# main.net
KiCad netlist of a schematic drawn in Altium Designer
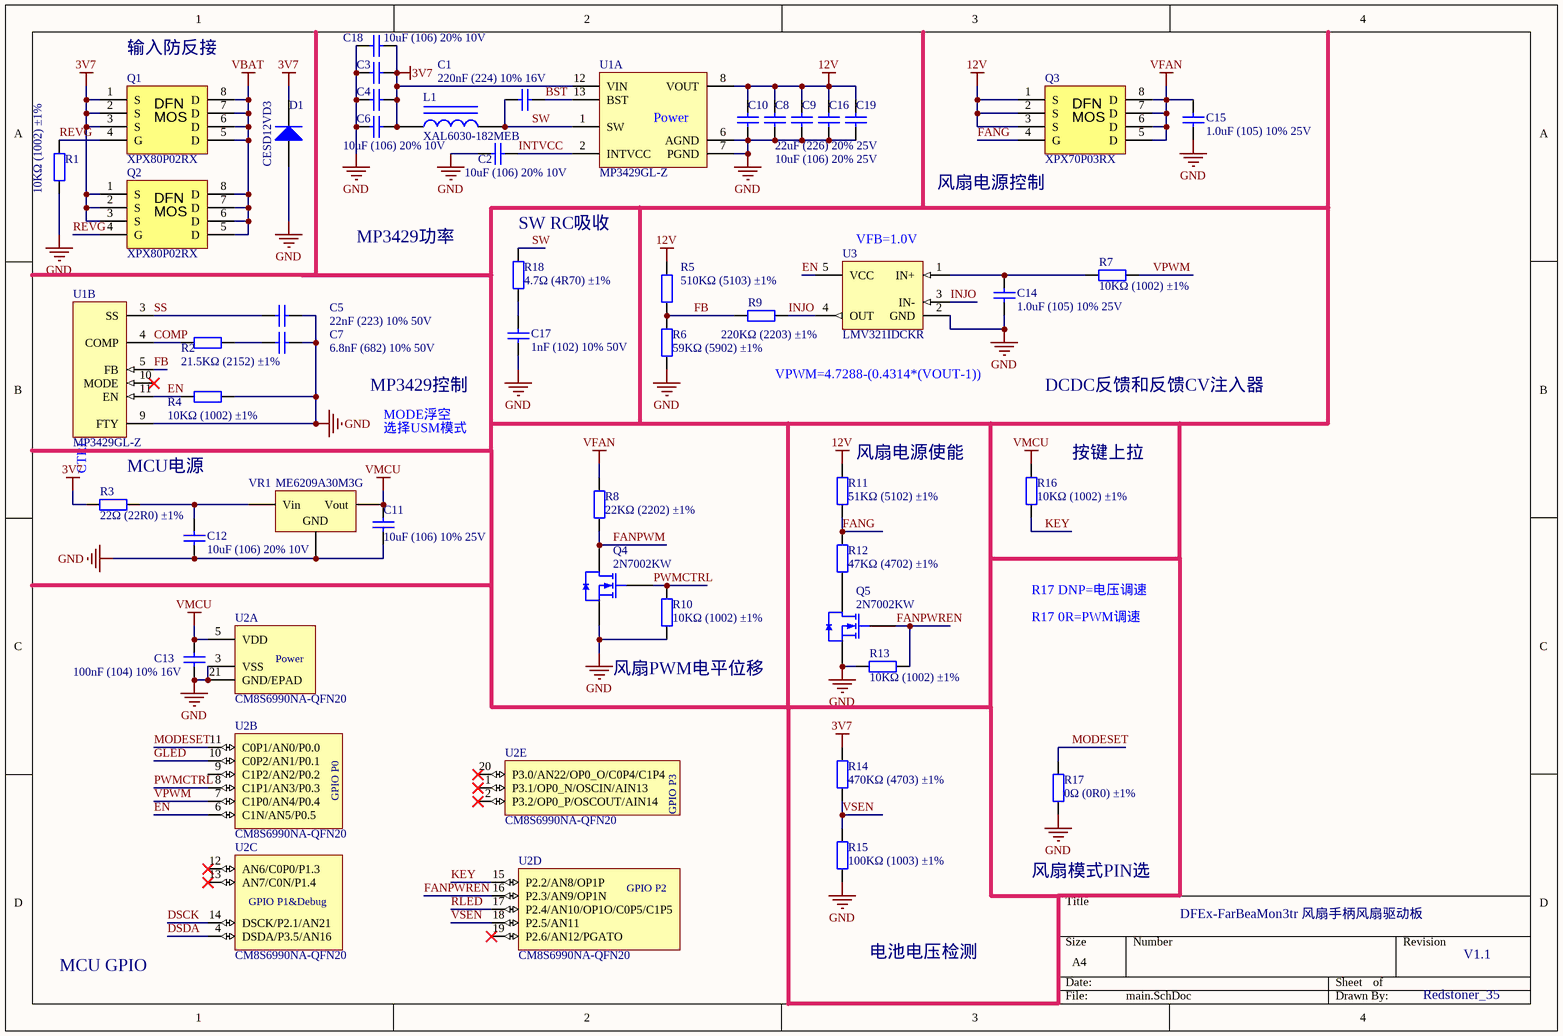
[diagram p0: main.SchDoc]

(export (version "E")
  (design (tool "Eeschema 10.0.6"))
  (components
    (comp (ref "C1")
      (value "220nF (224) 10% 16V")
      (footprint "0402_C")
      (description "贴片电容")
      (libsource (lib "Miscellaneous Devices LC") (part "0402 220nF (224) 10% 16V"))
    )
    (comp (ref "C2")
      (value "10uF (106) 20% 10V")
      (footprint "0402_C")
      (description "贴片电容")
      (libsource (lib "Miscellaneous Devices LC") (part "0402 10uF (106) 20% 6.3V"))
    )
    (comp (ref "C3")
      (value "47uF (476) 20% 10V")
      (footprint "0805_C")
      (description "贴片电容")
      (libsource (lib "Miscellaneous Devices LC") (part "0805 22uF (226) 20% 25V"))
    )
    (comp (ref "C4")
      (value "47uF (476) 20% 10V")
      (footprint "0805_C")
      (description "贴片电容")
      (libsource (lib "Miscellaneous Devices LC") (part "0805 22uF (226) 20% 25V"))
    )
    (comp (ref "C5")
      (value "22nF (223) 10% 50V")
      (footprint "0402_C")
      (description "贴片电容")
      (libsource (lib "Miscellaneous Devices LC") (part "0402 22nF (223) 10% 50V"))
    )
    (comp (ref "C6")
      (value "10uF (106) 20% 10V")
      (footprint "0402_C")
      (description "贴片电容")
      (libsource (lib "Miscellaneous Devices LC") (part "0402 10uF (106) 20% 6.3V"))
    )
    (comp (ref "C7")
      (value "6.8nF (682) 10% 50V")
      (footprint "0402_C")
      (description "贴片电容")
      (libsource (lib "Miscellaneous Devices LC") (part "0402 10nF (103) 10% 50V"))
    )
    (comp (ref "C8")
      (value "22uF (226) 20% 25V")
      (footprint "0805_C")
      (description "贴片电容")
      (libsource (lib "Miscellaneous Devices LC") (part "0805 22uF (226) 20% 25V"))
    )
    (comp (ref "C9")
      (value "22uF (226) 20% 25V")
      (footprint "0805_C")
      (description "贴片电容")
      (libsource (lib "Miscellaneous Devices LC") (part "0805 22uF (226) 20% 25V"))
    )
    (comp (ref "C10")
      (value "10uF (106) 20% 25V")
      (footprint "0603_C")
      (description "贴片电容")
      (libsource (lib "Miscellaneous Devices LC") (part "0603 4.7uF (475) 10% 16V"))
    )
    (comp (ref "C11")
      (value "10uF (106) 10% 25V")
      (footprint "0603_C")
      (description "贴片电容")
      (libsource (lib "Miscellaneous Devices LC") (part "0603 10uF (106) 10% 10V"))
    )
    (comp (ref "C12")
      (value "10uF (106) 20% 10V")
      (footprint "0402_C")
      (description "贴片电容")
      (libsource (lib "Miscellaneous Devices LC") (part "0402 10uF (106) 20% 6.3V"))
    )
    (comp (ref "C13")
      (value "100nF (104) 10% 16V")
      (footprint "0402_C")
      (description "贴片电容")
      (libsource (lib "Miscellaneous Devices LC") (part "0402 100nF (104) 10% 16V"))
    )
    (comp (ref "C14")
      (value "1.0uF (105) 10% 25V")
      (footprint "0402_C")
      (description "贴片电容")
      (libsource (lib "Miscellaneous Devices LC") (part "0402 1.0uF (105) 10% 25V"))
    )
    (comp (ref "C15")
      (value "1.0uF (105) 10% 25V")
      (footprint "0402_C")
      (description "贴片电容")
      (libsource (lib "Miscellaneous Devices LC") (part "0402 1.0uF (105) 10% 25V"))
    )
    (comp (ref "C16")
      (value "10uF (106) 20% 25V")
      (footprint "0603_C")
      (description "贴片电容")
      (libsource (lib "Miscellaneous Devices LC") (part "0603 4.7uF (475) 10% 16V"))
    )
    (comp (ref "C17")
      (value "1nF (102) 10% 50V")
      (footprint "0402_C")
      (description "贴片电容")
      (libsource (lib "Miscellaneous Devices LC") (part "0402 1nF (102) 10% 50V"))
    )
    (comp (ref "C18")
      (value "10uF (106) 20% 10V")
      (footprint "0402_C")
      (description "贴片电容")
      (libsource (lib "Miscellaneous Devices LC") (part "0402 10uF (106) 20% 6.3V"))
    )
    (comp (ref "C19")
      (value "10uF (106) 20% 25V")
      (footprint "0603_C")
      (description "贴片电容")
      (libsource (lib "Miscellaneous Devices LC") (part "0603 4.7uF (475) 10% 16V"))
    )
    (comp (ref "D1")
      (value "CESD12VD3")
      (footprint "SOD-323")
      (description "12V TVS二极管")
      (libsource (lib "Miscellaneous Devices LC") (part "SOD-323 1N4148WS T4"))
    )
    (comp (ref "L1")
      (value "XAL6030-182MEB")
      (footprint "XAL6030-xxxME")
      (description "Magnetic-Core Inductor")
      (fields (field (name "PUBLISHER") "Altium Limited"))
      (libsource (lib "Miscellaneous Devices") (part "Inductor Iron"))
    )
    (comp (ref "Q1")
      (value "XPX80P02RX")
      (footprint "DFN-8_L3.0-W3.0-P0.65-BL")
      (description "-20V -80A 4mR内阻 P沟道MOSFET")
      (libsource (lib "custom") (part "SON/DFN5x6 MOS"))
    )
    (comp (ref "Q2")
      (value "XPX80P02RX")
      (footprint "DFN-8_L3.0-W3.0-P0.65-BL")
      (description "-20V -80A 4mR内阻 P沟道MOSFET")
      (libsource (lib "custom") (part "SON/DFN5x6 MOS"))
    )
    (comp (ref "Q3")
      (value "XPX70P03RX")
      (footprint "DFN-8_L3.0-W3.0-P0.65-BL")
      (description "-30V -70A 6.5mR P沟道增强型MOSFET")
      (libsource (lib "custom") (part "SON/DFN5x6 MOS"))
    )
    (comp (ref "Q4")
      (value "2N7002KW")
      (footprint "SC70-3")
      (description "单N沟道MOSFET(场效应管)")
      (libsource (lib "Miscellaneous Devices LC") (part "2N7002 7002"))
    )
    (comp (ref "Q5")
      (value "2N7002KW")
      (footprint "SC70-3")
      (description "单N沟道MOSFET(场效应管)")
      (libsource (lib "Miscellaneous Devices LC") (part "2N7002 7002"))
    )
    (comp (ref "R1")
      (value "10KΩ (1002) ±1%")
      (footprint "0402_R")
      (description "贴片电阻")
      (libsource (lib "") (part "0402 10KΩ (1002) 1%_2"))
    )
    (comp (ref "R2")
      (value "21.5KΩ (2152) ±1%")
      (footprint "0402_R")
      (description "贴片电阻")
      (libsource (lib "Miscellaneous Devices LC") (part "0402 18KΩ (1802) 1%"))
    )
    (comp (ref "R3")
      (value "22Ω (22R0) ±1%")
      (footprint "0402_R")
      (description "贴片电阻")
      (libsource (lib "Miscellaneous Devices LC") (part "0402 22Ω (22R0) 1%"))
    )
    (comp (ref "R4")
      (value "10KΩ (1002) ±1%")
      (footprint "0402_R")
      (description "贴片电阻")
      (libsource (lib "Miscellaneous Devices LC") (part "0402 10KΩ (1002) 1%"))
    )
    (comp (ref "R5")
      (value "510KΩ (5103) ±1%")
      (footprint "0402_R")
      (description "贴片电阻")
      (libsource (lib "Miscellaneous Devices LC") (part "0402 510KΩ (5103) 1%"))
    )
    (comp (ref "R6")
      (value "59KΩ (5902) ±1%")
      (footprint "0402_R")
      (description "贴片电阻")
      (libsource (lib "Miscellaneous Devices LC") (part "0402 510KΩ (5103) 1%"))
    )
    (comp (ref "R7")
      (value "10KΩ (1002) ±1%")
      (footprint "0402_R")
      (description "贴片电阻")
      (libsource (lib "") (part "0402 10KΩ (1002) 1%_1"))
    )
    (comp (ref "R8")
      (value "22KΩ (2202) ±1%")
      (footprint "0402_R")
      (description "贴片电阻")
      (libsource (lib "Miscellaneous Devices LC") (part "0402 22KΩ (2202) 1%"))
    )
    (comp (ref "R9")
      (value "220KΩ (2203) ±1%")
      (footprint "0402_R")
      (description "贴片电阻")
      (libsource (lib "Miscellaneous Devices LC") (part "0402 100KΩ (1003) 1%"))
    )
    (comp (ref "R10")
      (value "10KΩ (1002) ±1%")
      (footprint "0402_R")
      (description "贴片电阻")
      (libsource (lib "") (part "0402 10KΩ (1002) 1%_2"))
    )
    (comp (ref "R11")
      (value "51KΩ (5102) ±1%")
      (footprint "0402_R")
      (description "贴片电阻")
      (libsource (lib "Miscellaneous Devices LC") (part "0402 47KΩ (4702) 1%"))
    )
    (comp (ref "R12")
      (value "47KΩ (4702) ±1%")
      (footprint "0402_R")
      (description "贴片电阻")
      (libsource (lib "Miscellaneous Devices LC") (part "0402 51KΩ (5102) 1%"))
    )
    (comp (ref "R13")
      (value "10KΩ (1002) ±1%")
      (footprint "0402_R")
      (description "贴片电阻")
      (libsource (lib "Miscellaneous Devices LC") (part "0402 10KΩ (1002) 1%"))
    )
    (comp (ref "R14")
      (value "470KΩ (4703) ±1%")
      (footprint "0402_R")
      (description "贴片电阻")
      (libsource (lib "Miscellaneous Devices LC") (part "0402 470KΩ (4703) 1%"))
    )
    (comp (ref "R15")
      (value "100KΩ (1003) ±1%")
      (footprint "0402_R")
      (description "贴片电阻")
      (libsource (lib "") (part "0402 100KΩ (1003) 1%_1"))
    )
    (comp (ref "R16")
      (value "10KΩ (1002) ±1%")
      (footprint "0402_R")
      (description "贴片电阻")
      (libsource (lib "") (part "0402 10KΩ (1002) 1%_2"))
    )
    (comp (ref "R17")
      (value "0Ω (0R0) ±1%")
      (footprint "0402_R")
      (description "贴片电阻")
      (libsource (lib "Miscellaneous Devices LC") (part "0402 0Ω (0R0) 1%"))
    )
    (comp (ref "R18")
      (value "4.7Ω (4R70) ±1%")
      (footprint "0402_R")
      (description "贴片电阻")
      (libsource (lib "Miscellaneous Devices LC") (part "0402 1Ω (1R00) 1%"))
    )
    (comp (ref "U1")
      (value "MP3429GL-Z")
      (footprint "QFN-MLP3*4-13L")
      (description "16VOUT, 21A Peak Current Fully Integrated Synchronous Boost Converter")
      (libsource (lib "custom") (part "MP3429GL-Z"))
    )
    (comp (ref "U2")
      (value "CM8S6990NA-QFN20")
      (footprint "QFN40P300X300X800_HS-21N")
      (description "增强型闪存1T 8051单片机，16KB Flash 256+1K XRAM")
      (libsource (lib "custom") (part "CM8S6990NA-QFN20"))
    )
    (comp (ref "U3")
      (value "LMV321IDCKR")
      (footprint "SC70-5")
      (description "CMOS超小型运算放大器，SC70-5")
      (libsource (lib "custom") (part "LMV321IDCKR"))
    )
    (comp (ref "VR1")
      (value "ME6209A30M3G")
      (footprint "SOT-23-3L")
      (description "低压差线性稳压(LDO)，输入耐压18V 输出3V 300mA最大电流 SOT23-3封装")
      (libsource (lib "Miscellaneous Devices LC") (part "SOT-23 XC6206P332MR"))
    )
  )
  (nets
    (net (code "1") (name "/BST") (class "Default")
      (node (ref "C1") (pin "2") (pinfunction "2_2") (pintype "passive"))
      (node (ref "U1") (pin "13") (pinfunction "BST_13") (pintype "power_in"))
    )
    (net (code "2") (name "/COMP") (class "Default")
      (node (ref "R2") (pin "1") (pinfunction "1_1") (pintype "passive"))
      (node (ref "U1") (pin "4") (pinfunction "COMP_4") (pintype "passive"))
    )
    (net (code "3") (name "/DSCK") (class "Default")
      (node (ref "U2") (pin "14") (pinfunction "DSCK/P2.1/AN21_14") (pintype "bidirectional"))
    )
    (net (code "4") (name "/DSDA") (class "Default")
      (node (ref "U2") (pin "4") (pinfunction "DSDA/P3.5/AN16_4") (pintype "bidirectional"))
    )
    (net (code "5") (name "/EN") (class "Default")
      (node (ref "R4") (pin "2") (pinfunction "2_2") (pintype "passive"))
      (node (ref "U1") (pin "11") (pinfunction "EN_11") (pintype "input"))
      (node (ref "U2") (pin "6") (pinfunction "C1N/AN5/P0.5_6") (pintype "bidirectional"))
      (node (ref "U3") (pin "5") (pinfunction "VCC_5") (pintype "power_in"))
    )
    (net (code "6") (name "/FANG") (class "Default")
      (node (ref "Q3") (pin "4") (pinfunction "G_4") (pintype "passive"))
      (node (ref "R11") (pin "1") (pinfunction "1_1") (pintype "passive"))
      (node (ref "R12") (pin "2") (pinfunction "2_2") (pintype "passive"))
    )
    (net (code "7") (name "/FANPWM") (class "Default")
      (node (ref "Q4") (pin "3") (pinfunction "D_3") (pintype "passive"))
      (node (ref "R8") (pin "1") (pinfunction "1_1") (pintype "passive"))
    )
    (net (code "8") (name "/FANPWREN") (class "Default")
      (node (ref "Q5") (pin "1") (pinfunction "G_1") (pintype "passive"))
      (node (ref "R13") (pin "1") (pinfunction "1_1") (pintype "passive"))
      (node (ref "U2") (pin "16") (pinfunction "P2.3/AN9/OP1N_16") (pintype "bidirectional"))
    )
    (net (code "9") (name "/FB") (class "Default")
      (node (ref "R5") (pin "1") (pinfunction "1_1") (pintype "passive"))
      (node (ref "R6") (pin "2") (pinfunction "2_2") (pintype "passive"))
      (node (ref "R9") (pin "1") (pinfunction "1_1") (pintype "passive"))
      (node (ref "U1") (pin "5") (pinfunction "FB_5") (pintype "input"))
    )
    (net (code "10") (name "/GLED") (class "Default")
      (node (ref "U2") (pin "10") (pinfunction "C0P2/AN1/P0.1_10") (pintype "bidirectional"))
    )
    (net (code "11") (name "/INJO") (class "Default")
      (node (ref "R9") (pin "2") (pinfunction "2_2") (pintype "passive"))
      (node (ref "U3") (pin "3") (pinfunction "IN-_3") (pintype "input"))
      (node (ref "U3") (pin "4") (pinfunction "OUT_4") (pintype "output"))
    )
    (net (code "12") (name "/INTVCC") (class "Default")
      (node (ref "C2") (pin "2") (pinfunction "2_2") (pintype "passive"))
      (node (ref "U1") (pin "2") (pinfunction "INTVCC_2") (pintype "power_in"))
    )
    (net (code "13") (name "/KEY") (class "Default")
      (node (ref "R16") (pin "1") (pinfunction "1_1") (pintype "passive"))
      (node (ref "U2") (pin "15") (pinfunction "P2.2/AN8/OP1P_15") (pintype "bidirectional"))
    )
    (net (code "14") (name "/MODESET") (class "Default")
      (node (ref "R17") (pin "2") (pinfunction "2_2") (pintype "passive"))
      (node (ref "U2") (pin "11") (pinfunction "C0P1/AN0/P0.0_11") (pintype "bidirectional"))
    )
    (net (code "15") (name "/PWMCTRL") (class "Default")
      (node (ref "Q4") (pin "1") (pinfunction "G_1") (pintype "passive"))
      (node (ref "R10") (pin "2") (pinfunction "2_2") (pintype "passive"))
      (node (ref "U2") (pin "8") (pinfunction "C1P1/AN3/P0.3_8") (pintype "bidirectional"))
    )
    (net (code "16") (name "/REVG") (class "Default")
      (node (ref "Q1") (pin "4") (pinfunction "G_4") (pintype "passive"))
      (node (ref "Q2") (pin "4") (pinfunction "G_4") (pintype "passive"))
      (node (ref "R1") (pin "2") (pinfunction "2_2") (pintype "passive"))
    )
    (net (code "17") (name "/RLED") (class "Default")
      (node (ref "U2") (pin "17") (pinfunction "P2.4/AN10/OP1O/C0P5/C1P5_17") (pintype "bidirectional"))
    )
    (net (code "18") (name "/SS") (class "Default")
      (node (ref "C5") (pin "1") (pinfunction "1_1") (pintype "passive"))
      (node (ref "U1") (pin "3") (pinfunction "SS_3") (pintype "passive"))
    )
    (net (code "19") (name "/SW") (class "Default")
      (node (ref "C1") (pin "1") (pinfunction "1_1") (pintype "passive"))
      (node (ref "L1") (pin "2") (pinfunction "2_2") (pintype "passive"))
      (node (ref "R18") (pin "2") (pinfunction "2_2") (pintype "passive"))
      (node (ref "U1") (pin "1") (pinfunction "SW_1") (pintype "power_in"))
    )
    (net (code "20") (name "/VPWM") (class "Default")
      (node (ref "R7") (pin "2") (pinfunction "2_2") (pintype "passive"))
      (node (ref "U2") (pin "7") (pinfunction "C1P0/AN4/P0.4_7") (pintype "bidirectional"))
    )
    (net (code "21") (name "/VSEN") (class "Default")
      (node (ref "R14") (pin "1") (pinfunction "1_1") (pintype "passive"))
      (node (ref "R15") (pin "2") (pinfunction "2_2") (pintype "passive"))
      (node (ref "U2") (pin "18") (pinfunction "P2.5/AN11_18") (pintype "bidirectional"))
    )
    (net (code "22") (name "3V7") (class "Default")
      (node (ref "C18") (pin "2") (pinfunction "2_2") (pintype "passive"))
      (node (ref "C3") (pin "2") (pinfunction "2_2") (pintype "passive"))
      (node (ref "C4") (pin "2") (pinfunction "2_2") (pintype "passive"))
      (node (ref "C6") (pin "2") (pinfunction "2_2") (pintype "passive"))
      (node (ref "D1") (pin "2") (pinfunction "K_2") (pintype "passive"))
      (node (ref "L1") (pin "1") (pinfunction "1_1") (pintype "passive"))
      (node (ref "Q1") (pin "1") (pinfunction "S_1") (pintype "passive"))
      (node (ref "Q1") (pin "2") (pinfunction "S_2") (pintype "passive"))
      (node (ref "Q1") (pin "3") (pinfunction "S_3") (pintype "passive"))
      (node (ref "Q2") (pin "1") (pinfunction "S_1") (pintype "passive"))
      (node (ref "Q2") (pin "2") (pinfunction "S_2") (pintype "passive"))
      (node (ref "Q2") (pin "3") (pinfunction "S_3") (pintype "passive"))
      (node (ref "R14") (pin "2") (pinfunction "2_2") (pintype "passive"))
      (node (ref "R3") (pin "1") (pinfunction "1_1") (pintype "passive"))
      (node (ref "U1") (pin "12") (pinfunction "VIN_12") (pintype "power_in"))
    )
    (net (code "23") (name "12V") (class "Default")
      (node (ref "C10") (pin "2") (pinfunction "2_2") (pintype "passive"))
      (node (ref "C16") (pin "2") (pinfunction "2_2") (pintype "passive"))
      (node (ref "C19") (pin "2") (pinfunction "2_2") (pintype "passive"))
      (node (ref "C8") (pin "2") (pinfunction "2_2") (pintype "passive"))
      (node (ref "C9") (pin "2") (pinfunction "2_2") (pintype "passive"))
      (node (ref "Q3") (pin "1") (pinfunction "S_1") (pintype "passive"))
      (node (ref "Q3") (pin "2") (pinfunction "S_2") (pintype "passive"))
      (node (ref "Q3") (pin "3") (pinfunction "S_3") (pintype "passive"))
      (node (ref "R11") (pin "2") (pinfunction "2_2") (pintype "passive"))
      (node (ref "R5") (pin "2") (pinfunction "2_2") (pintype "passive"))
      (node (ref "U1") (pin "8") (pinfunction "VOUT_8") (pintype "power_in"))
    )
    (net (code "24") (name "GND") (class "Default")
      (node (ref "C10") (pin "1") (pinfunction "1_1") (pintype "passive"))
      (node (ref "C11") (pin "1") (pinfunction "1_1") (pintype "passive"))
      (node (ref "C12") (pin "1") (pinfunction "1_1") (pintype "passive"))
      (node (ref "C13") (pin "1") (pinfunction "1_1") (pintype "passive"))
      (node (ref "C14") (pin "1") (pinfunction "1_1") (pintype "passive"))
      (node (ref "C15") (pin "1") (pinfunction "1_1") (pintype "passive"))
      (node (ref "C16") (pin "1") (pinfunction "1_1") (pintype "passive"))
      (node (ref "C17") (pin "1") (pinfunction "1_1") (pintype "passive"))
      (node (ref "C18") (pin "1") (pinfunction "1_1") (pintype "passive"))
      (node (ref "C19") (pin "1") (pinfunction "1_1") (pintype "passive"))
      (node (ref "C2") (pin "1") (pinfunction "1_1") (pintype "passive"))
      (node (ref "C3") (pin "1") (pinfunction "1_1") (pintype "passive"))
      (node (ref "C4") (pin "1") (pinfunction "1_1") (pintype "passive"))
      (node (ref "C5") (pin "2") (pinfunction "2_2") (pintype "passive"))
      (node (ref "C6") (pin "1") (pinfunction "1_1") (pintype "passive"))
      (node (ref "C7") (pin "2") (pinfunction "2_2") (pintype "passive"))
      (node (ref "C8") (pin "1") (pinfunction "1_1") (pintype "passive"))
      (node (ref "C9") (pin "1") (pinfunction "1_1") (pintype "passive"))
      (node (ref "D1") (pin "1") (pinfunction "A_1") (pintype "passive"))
      (node (ref "Q4") (pin "2") (pinfunction "S_2") (pintype "passive"))
      (node (ref "Q5") (pin "2") (pinfunction "S_2") (pintype "passive"))
      (node (ref "R1") (pin "1") (pinfunction "1_1") (pintype "passive"))
      (node (ref "R10") (pin "1") (pinfunction "1_1") (pintype "passive"))
      (node (ref "R13") (pin "2") (pinfunction "2_2") (pintype "passive"))
      (node (ref "R15") (pin "1") (pinfunction "1_1") (pintype "passive"))
      (node (ref "R17") (pin "1") (pinfunction "1_1") (pintype "passive"))
      (node (ref "R4") (pin "1") (pinfunction "1_1") (pintype "passive"))
      (node (ref "R6") (pin "1") (pinfunction "1_1") (pintype "passive"))
      (node (ref "U1") (pin "6") (pinfunction "AGND_6") (pintype "power_in"))
      (node (ref "U1") (pin "7") (pinfunction "PGND_7") (pintype "power_in"))
      (node (ref "U1") (pin "9") (pinfunction "FTY_9") (pintype "passive"))
      (node (ref "U2") (pin "21") (pinfunction "GND/EPAD_21") (pintype "power_in"))
      (node (ref "U2") (pin "3") (pinfunction "VSS_3") (pintype "power_in"))
      (node (ref "U3") (pin "2") (pinfunction "GND_2") (pintype "power_in"))
      (node (ref "VR1") (pin "1") (pinfunction "GND_1") (pintype "passive"))
    )
    (net (code "25") (name "Net-(C7-Pad1)") (class "Default")
      (node (ref "C7") (pin "1") (pinfunction "1_1") (pintype "passive"))
      (node (ref "R2") (pin "2") (pinfunction "2_2") (pintype "passive"))
    )
    (net (code "26") (name "Net-(C17-Pad2)") (class "Default")
      (node (ref "C17") (pin "2") (pinfunction "2_2") (pintype "passive"))
      (node (ref "R18") (pin "1") (pinfunction "1_1") (pintype "passive"))
    )
    (net (code "27") (name "Net-(Q5-D)") (class "Default")
      (node (ref "Q5") (pin "3") (pinfunction "D_3") (pintype "passive"))
      (node (ref "R12") (pin "1") (pinfunction "1_1") (pintype "passive"))
    )
    (net (code "28") (name "Net-(U3-IN+)") (class "Default")
      (node (ref "C14") (pin "2") (pinfunction "2_2") (pintype "passive"))
      (node (ref "R7") (pin "1") (pinfunction "1_1") (pintype "passive"))
      (node (ref "U3") (pin "1") (pinfunction "IN+_1") (pintype "input"))
    )
    (net (code "29") (name "Net-(VR1-Vin)") (class "Default")
      (node (ref "C12") (pin "2") (pinfunction "2_2") (pintype "passive"))
      (node (ref "R3") (pin "2") (pinfunction "2_2") (pintype "passive"))
      (node (ref "VR1") (pin "3") (pinfunction "Vin_3") (pintype "passive"))
    )
    (net (code "30") (name "VBAT") (class "Default")
      (node (ref "Q1") (pin "5") (pinfunction "D_5") (pintype "passive"))
      (node (ref "Q1") (pin "6") (pinfunction "D_6") (pintype "passive"))
      (node (ref "Q1") (pin "7") (pinfunction "D_7") (pintype "passive"))
      (node (ref "Q1") (pin "8") (pinfunction "D_8") (pintype "passive"))
      (node (ref "Q2") (pin "5") (pinfunction "D_5") (pintype "passive"))
      (node (ref "Q2") (pin "6") (pinfunction "D_6") (pintype "passive"))
      (node (ref "Q2") (pin "7") (pinfunction "D_7") (pintype "passive"))
      (node (ref "Q2") (pin "8") (pinfunction "D_8") (pintype "passive"))
    )
    (net (code "31") (name "VFAN") (class "Default")
      (node (ref "C15") (pin "2") (pinfunction "2_2") (pintype "passive"))
      (node (ref "Q3") (pin "5") (pinfunction "D_5") (pintype "passive"))
      (node (ref "Q3") (pin "6") (pinfunction "D_6") (pintype "passive"))
      (node (ref "Q3") (pin "7") (pinfunction "D_7") (pintype "passive"))
      (node (ref "Q3") (pin "8") (pinfunction "D_8") (pintype "passive"))
      (node (ref "R8") (pin "2") (pinfunction "2_2") (pintype "passive"))
    )
    (net (code "32") (name "VMCU") (class "Default")
      (node (ref "C11") (pin "2") (pinfunction "2_2") (pintype "passive"))
      (node (ref "C13") (pin "2") (pinfunction "2_2") (pintype "passive"))
      (node (ref "R16") (pin "2") (pinfunction "2_2") (pintype "passive"))
      (node (ref "U2") (pin "5") (pinfunction "VDD_5") (pintype "power_in"))
      (node (ref "VR1") (pin "2") (pinfunction "Vout_2") (pintype "passive"))
    )
    (net (code "33") (name "unconnected-(U1B-MODE-Pad10)") (class "Default")
      (node (ref "U1") (pin "10") (pinfunction "MODE_10") (pintype "input+no_connect"))
    )
    (net (code "34") (name "unconnected-(U2B-C1P2{slash}AN2{slash}P0.2-Pad9)") (class "Default")
      (node (ref "U2") (pin "9") (pinfunction "C1P2/AN2/P0.2_9") (pintype "bidirectional"))
    )
    (net (code "35") (name "unconnected-(U2C-AN6{slash}C0P0{slash}P1.3-Pad12)") (class "Default")
      (node (ref "U2") (pin "12") (pinfunction "AN6/C0P0/P1.3_12") (pintype "bidirectional+no_connect"))
    )
    (net (code "36") (name "unconnected-(U2C-AN7{slash}C0N{slash}P1.4-Pad13)") (class "Default")
      (node (ref "U2") (pin "13") (pinfunction "AN7/C0N/P1.4_13") (pintype "bidirectional+no_connect"))
    )
    (net (code "37") (name "unconnected-(U2D-P2.6{slash}AN12{slash}PGATO-Pad19)") (class "Default")
      (node (ref "U2") (pin "19") (pinfunction "P2.6/AN12/PGATO_19") (pintype "bidirectional+no_connect"))
    )
    (net (code "38") (name "unconnected-(U2E-P3.0{slash}AN22{slash}OP0_O{slash}C0P4{slash}C1P4-Pad20)") (class "Default")
      (node (ref "U2") (pin "20") (pinfunction "P3.0/AN22/OP0_O/C0P4/C1P4_20") (pintype "bidirectional+no_connect"))
    )
    (net (code "39") (name "unconnected-(U2E-P3.1{slash}OP0_N{slash}OSCIN{slash}AIN13-Pad1)") (class "Default")
      (node (ref "U2") (pin "1") (pinfunction "P3.1/OP0_N/OSCIN/AIN13_1") (pintype "bidirectional+no_connect"))
    )
    (net (code "40") (name "unconnected-(U2E-P3.2{slash}OP0_P{slash}OSCOUT{slash}AIN14-Pad2)") (class "Default")
      (node (ref "U2") (pin "2") (pinfunction "P3.2/OP0_P/OSCOUT/AIN14_2") (pintype "bidirectional+no_connect"))
    )
  )
)
